# 12-UART_CAN.net
KiCad netlist of a schematic drawn in Altium Designer
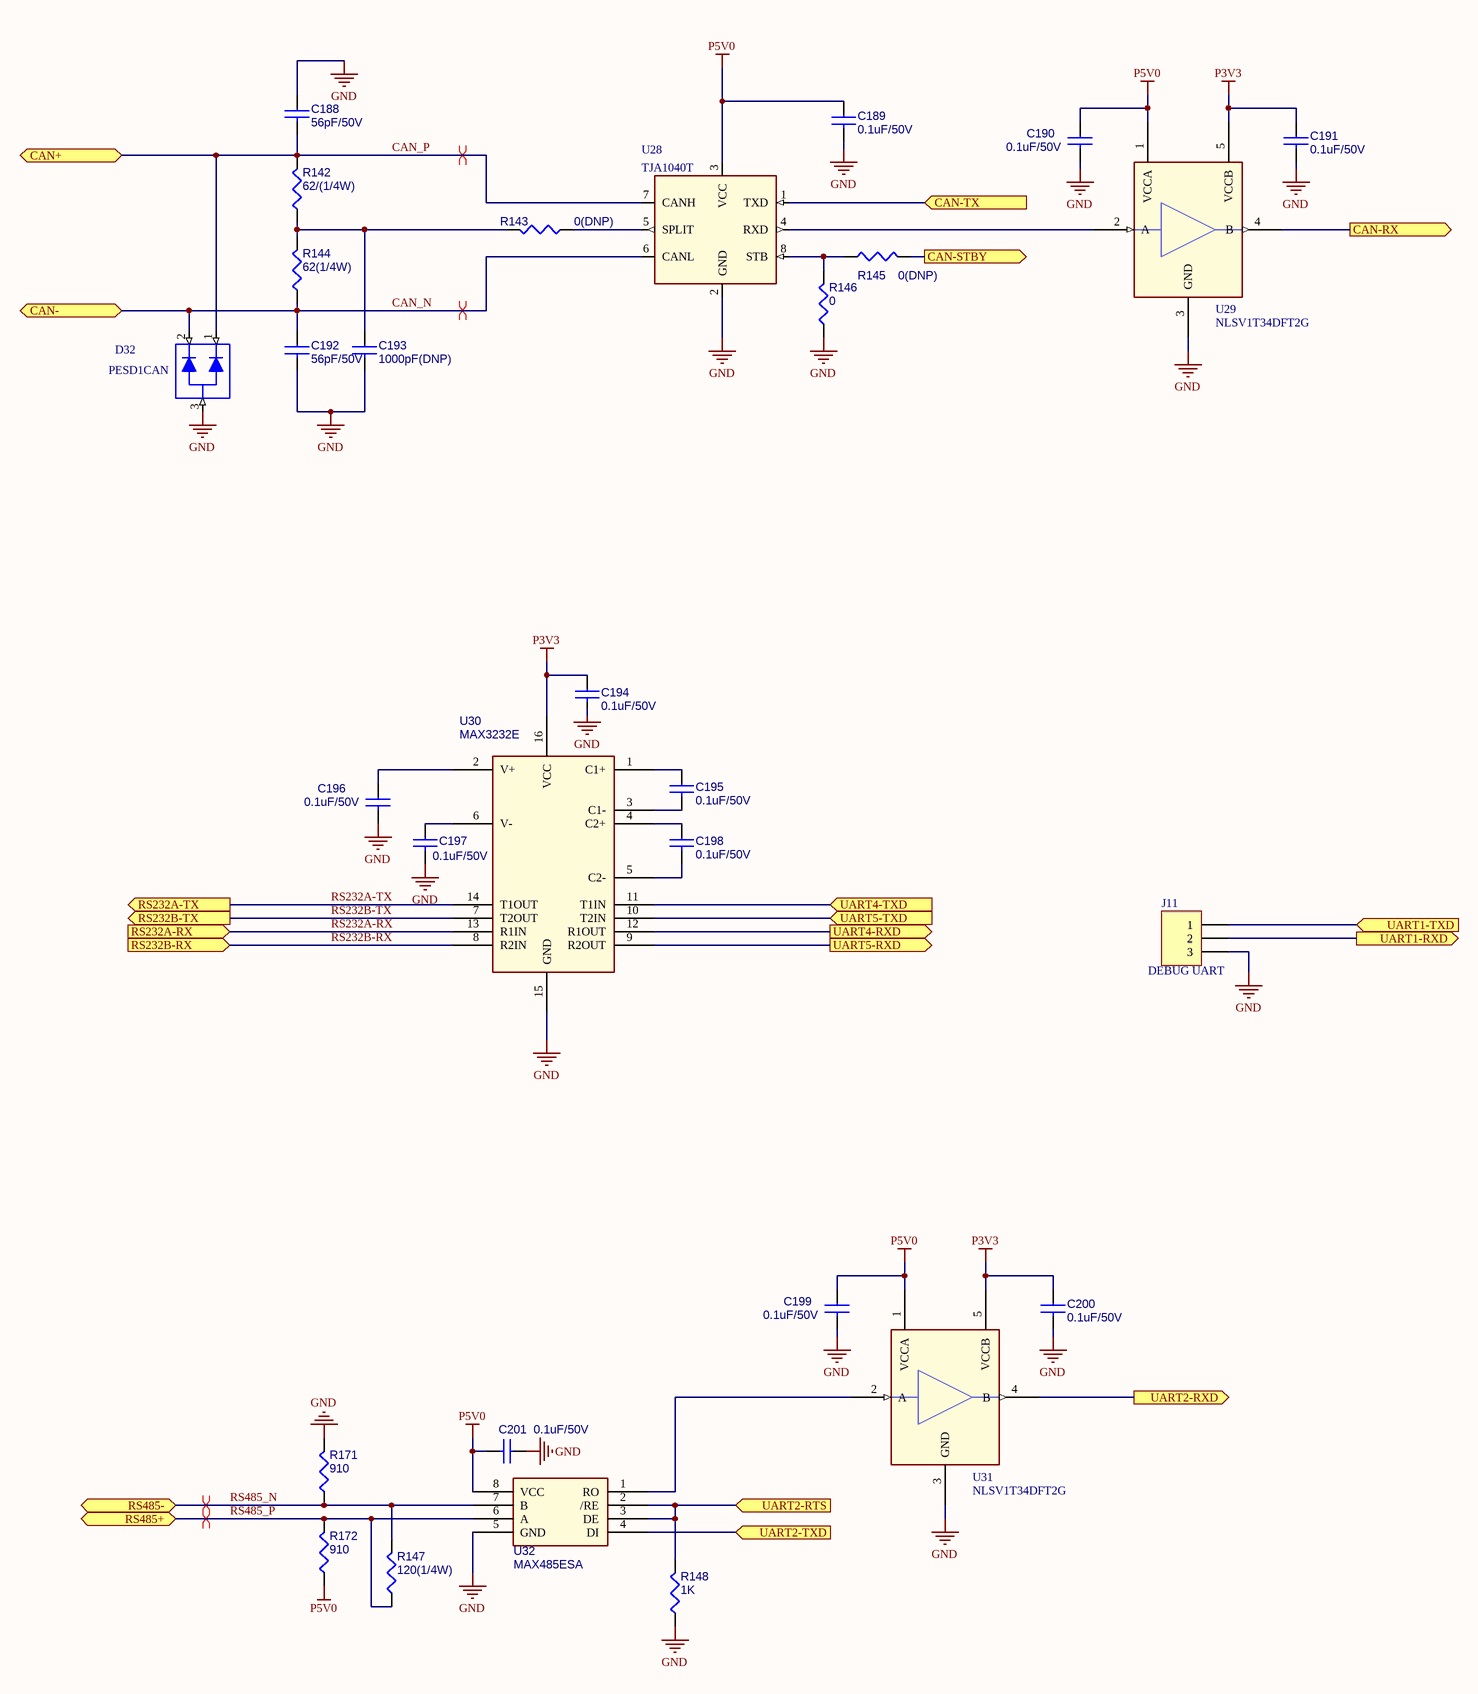
[diagram p0: 12-UART_CAN.SchDoc]

(export (version "E")
  (design (tool "Eeschema 10.0.6"))
  (components
    (comp (ref "C188") (value "56pF/50V") (libsource (lib "*") (part "P_CAP NP")))
    (comp (ref "C189") (value "0.1uF/50V") (libsource (lib "*") (part "P_CAP NP")))
    (comp (ref "C190") (value "0.1uF/50V") (libsource (lib "*") (part "P_CAP NP")))
    (comp (ref "C191") (value "0.1uF/50V") (libsource (lib "*") (part "P_CAP NP")))
    (comp (ref "C192") (value "56pF/50V") (libsource (lib "*") (part "P_CAP NP")))
    (comp (ref "C193") (value "1000pF(DNP)") (libsource (lib "*") (part "P_CAP NP")))
    (comp (ref "C194") (value "0.1uF/50V") (libsource (lib "*") (part "CAP")))
    (comp (ref "C195") (value "0.1uF/50V") (libsource (lib "*") (part "CAP")))
    (comp (ref "C196") (value "0.1uF/50V") (libsource (lib "*") (part "CAP")))
    (comp (ref "C197") (value "0.1uF/50V") (libsource (lib "*") (part "CAP")))
    (comp (ref "C198") (value "0.1uF/50V") (libsource (lib "*") (part "CAP")))
    (comp (ref "C199") (value "0.1uF/50V") (libsource (lib "*") (part "P_CAP NP")))
    (comp (ref "C200") (value "0.1uF/50V") (libsource (lib "*") (part "P_CAP NP")))
    (comp (ref "C201")
      (value "0.1uF/50V")
      (fields (field (name "PART NUMBER") "SE132225K8L"))
      (libsource (lib "*") (part "P_CAP NP"))
    )
    (comp (ref "D32")
      (value "PESD1CAN")
      (footprint "PESD2CAN")
      (fields (field (name "PART NUMBER") "SCA00000J00"))
      (libsource (lib "Schlib") (part "PESD2CAN"))
    )
    (comp (ref "J11")
      (value "DEBUG UART")
      (footprint "HDR1X3")
      (description "Header, 3-Pin")
      (fields (field (name "PUBLISHER") "Altium Limited"))
      (libsource (lib "Miscellaneous Connectors") (part "Header 3"))
    )
    (comp (ref "R142") (value "62/(1/4W)") (footprint "1206") (libsource (lib "*") (part "P_R")))
    (comp (ref "R143") (value "0(DNP)") (footprint "0402") (libsource (lib "*") (part "P_R")))
    (comp (ref "R144") (value "62(1/4W)") (footprint "1206") (libsource (lib "*") (part "P_R")))
    (comp (ref "R145") (value "0(DNP)") (footprint "0402") (libsource (lib "*") (part "P_R")))
    (comp (ref "R146") (value "0") (footprint "0402") (libsource (lib "*") (part "P_R")))
    (comp (ref "R147")
      (value "120(1/4W)")
      (fields (field (name "PART NUMBER") "SD02810028L"))
      (libsource (lib "*") (part "R"))
    )
    (comp (ref "R148")
      (value "1K")
      (fields (field (name "PART NUMBER") "SD02810028L"))
      (libsource (lib "*") (part "R"))
    )
    (comp (ref "R171")
      (value "910")
      (fields (field (name "PART NUMBER") "SD02810028L"))
      (libsource (lib "*") (part "R"))
    )
    (comp (ref "R172")
      (value "910")
      (fields (field (name "PART NUMBER") "SD02810028L"))
      (libsource (lib "*") (part "R"))
    )
    (comp (ref "U28")
      (value "TJA1040T")
      (footprint "SO8")
      (description "IC XCVR CAN HS 5V SO8")
      (libsource (lib "*") (part "TJA1040T_SO_8P"))
    )
    (comp (ref "U29")
      (value "NLSV1T34DFT2G")
      (footprint "SC70")
      (libsource (lib "Schlib") (part "NLSV1T34DFT2G"))
    )
    (comp (ref "U30") (value "MAX3232E") (footprint "SO-16") (libsource (lib "*") (part "MAX3232")))
    (comp (ref "U31")
      (value "NLSV1T34DFT2G")
      (footprint "SC70")
      (libsource (lib "Schlib") (part "NLSV1T34DFT2G"))
    )
    (comp (ref "U32") (value "MAX485ESA") (libsource (lib "*") (part "MAX485")))
  )
  (nets
    (net (code "1") (name "/CAN-RX") (class "Default")
      (node (ref "U29") (pin "4") (pinfunction "B_4") (pintype "output"))
    )
    (net (code "2") (name "/CAN-STBY") (class "Default")
      (node (ref "R145") (pin "1") (pinfunction "1_1") (pintype "passive"))
    )
    (net (code "3") (name "/CAN-TX") (class "Default")
      (node (ref "U28") (pin "1") (pinfunction "TXD_1") (pintype "input"))
    )
    (net (code "4") (name "/CAN_N") (class "Default")
      (node (ref "C192") (pin "1") (pinfunction "1_1") (pintype "passive"))
      (node (ref "D32") (pin "2") (pinfunction "2_2") (pintype "input"))
      (node (ref "R144") (pin "2") (pinfunction "2_2") (pintype "passive"))
      (node (ref "U28") (pin "6") (pinfunction "CANL_6") (pintype "bidirectional"))
    )
    (net (code "5") (name "/CAN_P") (class "Default")
      (node (ref "C188") (pin "2") (pinfunction "2_2") (pintype "passive"))
      (node (ref "D32") (pin "1") (pinfunction "1_1") (pintype "input"))
      (node (ref "R142") (pin "1") (pinfunction "1_1") (pintype "passive"))
      (node (ref "U28") (pin "7") (pinfunction "CANH_7") (pintype "bidirectional"))
    )
    (net (code "6") (name "/RS232A-RX") (class "Default")
      (node (ref "U30") (pin "13") (pinfunction "R1IN_13") (pintype "passive"))
    )
    (net (code "7") (name "/RS232A-TX") (class "Default")
      (node (ref "U30") (pin "14") (pinfunction "T1OUT_14") (pintype "passive"))
    )
    (net (code "8") (name "/RS232B-RX") (class "Default")
      (node (ref "U30") (pin "8") (pinfunction "R2IN_8") (pintype "passive"))
    )
    (net (code "9") (name "/RS232B-TX") (class "Default")
      (node (ref "U30") (pin "7") (pinfunction "T2OUT_7") (pintype "passive"))
    )
    (net (code "10") (name "/RS485_N") (class "Default")
      (node (ref "R147") (pin "1") (pinfunction "1_1") (pintype "passive"))
      (node (ref "R171") (pin "2") (pinfunction "2_2") (pintype "passive"))
      (node (ref "U32") (pin "7") (pinfunction "B_7") (pintype "passive"))
    )
    (net (code "11") (name "/RS485_P") (class "Default")
      (node (ref "R147") (pin "2") (pinfunction "2_2") (pintype "passive"))
      (node (ref "R172") (pin "1") (pinfunction "1_1") (pintype "passive"))
      (node (ref "U32") (pin "6") (pinfunction "A_6") (pintype "passive"))
    )
    (net (code "12") (name "/UART1-RXD") (class "Default")
      (node (ref "J11") (pin "2") (pinfunction "2_2") (pintype "passive"))
    )
    (net (code "13") (name "/UART1-TXD") (class "Default")
      (node (ref "J11") (pin "1") (pinfunction "1_1") (pintype "passive"))
    )
    (net (code "14") (name "/UART2-RTS") (class "Default")
      (node (ref "R148") (pin "1") (pinfunction "1_1") (pintype "passive"))
      (node (ref "U32") (pin "2") (pinfunction "/RE_2") (pintype "passive"))
      (node (ref "U32") (pin "3") (pinfunction "DE_3") (pintype "passive"))
    )
    (net (code "15") (name "/UART2-RXD") (class "Default")
      (node (ref "U31") (pin "4") (pinfunction "B_4") (pintype "output"))
    )
    (net (code "16") (name "/UART2-TXD") (class "Default")
      (node (ref "U32") (pin "4") (pinfunction "DI_4") (pintype "passive"))
    )
    (net (code "17") (name "/UART4-RXD") (class "Default")
      (node (ref "U30") (pin "12") (pinfunction "R1OUT_12") (pintype "passive"))
    )
    (net (code "18") (name "/UART4-TXD") (class "Default")
      (node (ref "U30") (pin "11") (pinfunction "T1IN_11") (pintype "passive"))
    )
    (net (code "19") (name "/UART5-RXD") (class "Default")
      (node (ref "U30") (pin "9") (pinfunction "R2OUT_9") (pintype "passive"))
    )
    (net (code "20") (name "/UART5-TXD") (class "Default")
      (node (ref "U30") (pin "10") (pinfunction "T2IN_10") (pintype "passive"))
    )
    (net (code "21") (name "GND") (class "Default")
      (node (ref "C188") (pin "1") (pinfunction "1_1") (pintype "passive"))
      (node (ref "C189") (pin "2") (pinfunction "2_2") (pintype "passive"))
      (node (ref "C190") (pin "2") (pinfunction "2_2") (pintype "passive"))
      (node (ref "C191") (pin "2") (pinfunction "2_2") (pintype "passive"))
      (node (ref "C192") (pin "2") (pinfunction "2_2") (pintype "passive"))
      (node (ref "C193") (pin "2") (pinfunction "2_2") (pintype "passive"))
      (node (ref "C194") (pin "2") (pinfunction "2_2") (pintype "passive"))
      (node (ref "C196") (pin "2") (pinfunction "2_2") (pintype "passive"))
      (node (ref "C197") (pin "2") (pinfunction "2_2") (pintype "passive"))
      (node (ref "C199") (pin "2") (pinfunction "2_2") (pintype "passive"))
      (node (ref "C200") (pin "2") (pinfunction "2_2") (pintype "passive"))
      (node (ref "C201") (pin "1") (pinfunction "1_1") (pintype "passive"))
      (node (ref "D32") (pin "3") (pinfunction "3_3") (pintype "input"))
      (node (ref "J11") (pin "3") (pinfunction "3_3") (pintype "passive"))
      (node (ref "R146") (pin "2") (pinfunction "2_2") (pintype "passive"))
      (node (ref "R148") (pin "2") (pinfunction "2_2") (pintype "passive"))
      (node (ref "R171") (pin "1") (pinfunction "1_1") (pintype "passive"))
      (node (ref "U28") (pin "2") (pinfunction "GND_2") (pintype "power_in"))
      (node (ref "U29") (pin "3") (pinfunction "GND_3") (pintype "power_in"))
      (node (ref "U30") (pin "15") (pinfunction "GND_15") (pintype "passive"))
      (node (ref "U31") (pin "3") (pinfunction "GND_3") (pintype "power_in"))
      (node (ref "U32") (pin "5") (pinfunction "GND_5") (pintype "passive"))
    )
    (net (code "22") (name "Net-(C193-Pad1)") (class "Default")
      (node (ref "C193") (pin "1") (pinfunction "1_1") (pintype "passive"))
      (node (ref "R142") (pin "2") (pinfunction "2_2") (pintype "passive"))
      (node (ref "R143") (pin "1") (pinfunction "1_1") (pintype "passive"))
      (node (ref "R144") (pin "1") (pinfunction "1_1") (pintype "passive"))
    )
    (net (code "23") (name "Net-(U28-RXD)") (class "Default")
      (node (ref "U28") (pin "4") (pinfunction "RXD_4") (pintype "output"))
      (node (ref "U29") (pin "2") (pinfunction "A_2") (pintype "input"))
    )
    (net (code "24") (name "Net-(U28-SPLIT)") (class "Default")
      (node (ref "R143") (pin "2") (pinfunction "2_2") (pintype "passive"))
      (node (ref "U28") (pin "5") (pinfunction "SPLIT_5") (pintype "output"))
    )
    (net (code "25") (name "Net-(U28-STB)") (class "Default")
      (node (ref "R145") (pin "2") (pinfunction "2_2") (pintype "passive"))
      (node (ref "R146") (pin "1") (pinfunction "1_1") (pintype "passive"))
      (node (ref "U28") (pin "8") (pinfunction "STB_8") (pintype "input"))
    )
    (net (code "26") (name "Net-(U30-C1+)") (class "Default")
      (node (ref "C195") (pin "1") (pinfunction "1_1") (pintype "passive"))
      (node (ref "U30") (pin "1") (pinfunction "C1+_1") (pintype "passive"))
    )
    (net (code "27") (name "Net-(U30-C1-)") (class "Default")
      (node (ref "C195") (pin "2") (pinfunction "2_2") (pintype "passive"))
      (node (ref "U30") (pin "3") (pinfunction "C1-_3") (pintype "passive"))
    )
    (net (code "28") (name "Net-(U30-C2+)") (class "Default")
      (node (ref "C198") (pin "1") (pinfunction "1_1") (pintype "passive"))
      (node (ref "U30") (pin "4") (pinfunction "C2+_4") (pintype "passive"))
    )
    (net (code "29") (name "Net-(U30-C2-)") (class "Default")
      (node (ref "C198") (pin "2") (pinfunction "2_2") (pintype "passive"))
      (node (ref "U30") (pin "5") (pinfunction "C2-_5") (pintype "passive"))
    )
    (net (code "30") (name "Net-(U30-V+)") (class "Default")
      (node (ref "C196") (pin "1") (pinfunction "1_1") (pintype "passive"))
      (node (ref "U30") (pin "2") (pinfunction "V+_2") (pintype "passive"))
    )
    (net (code "31") (name "Net-(U30-V-)") (class "Default")
      (node (ref "C197") (pin "1") (pinfunction "1_1") (pintype "passive"))
      (node (ref "U30") (pin "6") (pinfunction "V-_6") (pintype "passive"))
    )
    (net (code "32") (name "Net-(U31-A)") (class "Default")
      (node (ref "U31") (pin "2") (pinfunction "A_2") (pintype "input"))
      (node (ref "U32") (pin "1") (pinfunction "RO_1") (pintype "passive"))
    )
    (net (code "33") (name "P3V3") (class "Default")
      (node (ref "C191") (pin "1") (pinfunction "1_1") (pintype "passive"))
      (node (ref "C194") (pin "1") (pinfunction "1_1") (pintype "passive"))
      (node (ref "C200") (pin "1") (pinfunction "1_1") (pintype "passive"))
      (node (ref "U29") (pin "5") (pinfunction "VCCB_5") (pintype "power_in"))
      (node (ref "U30") (pin "16") (pinfunction "VCC_16") (pintype "passive"))
      (node (ref "U31") (pin "5") (pinfunction "VCCB_5") (pintype "power_in"))
    )
    (net (code "34") (name "P5V0") (class "Default")
      (node (ref "C189") (pin "1") (pinfunction "1_1") (pintype "passive"))
      (node (ref "C190") (pin "1") (pinfunction "1_1") (pintype "passive"))
      (node (ref "C199") (pin "1") (pinfunction "1_1") (pintype "passive"))
      (node (ref "C201") (pin "2") (pinfunction "2_2") (pintype "passive"))
      (node (ref "R172") (pin "2") (pinfunction "2_2") (pintype "passive"))
      (node (ref "U28") (pin "3") (pinfunction "VCC_3") (pintype "power_in"))
      (node (ref "U29") (pin "1") (pinfunction "VCCA_1") (pintype "power_in"))
      (node (ref "U31") (pin "1") (pinfunction "VCCA_1") (pintype "power_in"))
      (node (ref "U32") (pin "8") (pinfunction "VCC_8") (pintype "passive"))
    )
  )
)
